# 6coils-1-discrete.net
KiCad netlist of a schematic drawn in EasyEDA
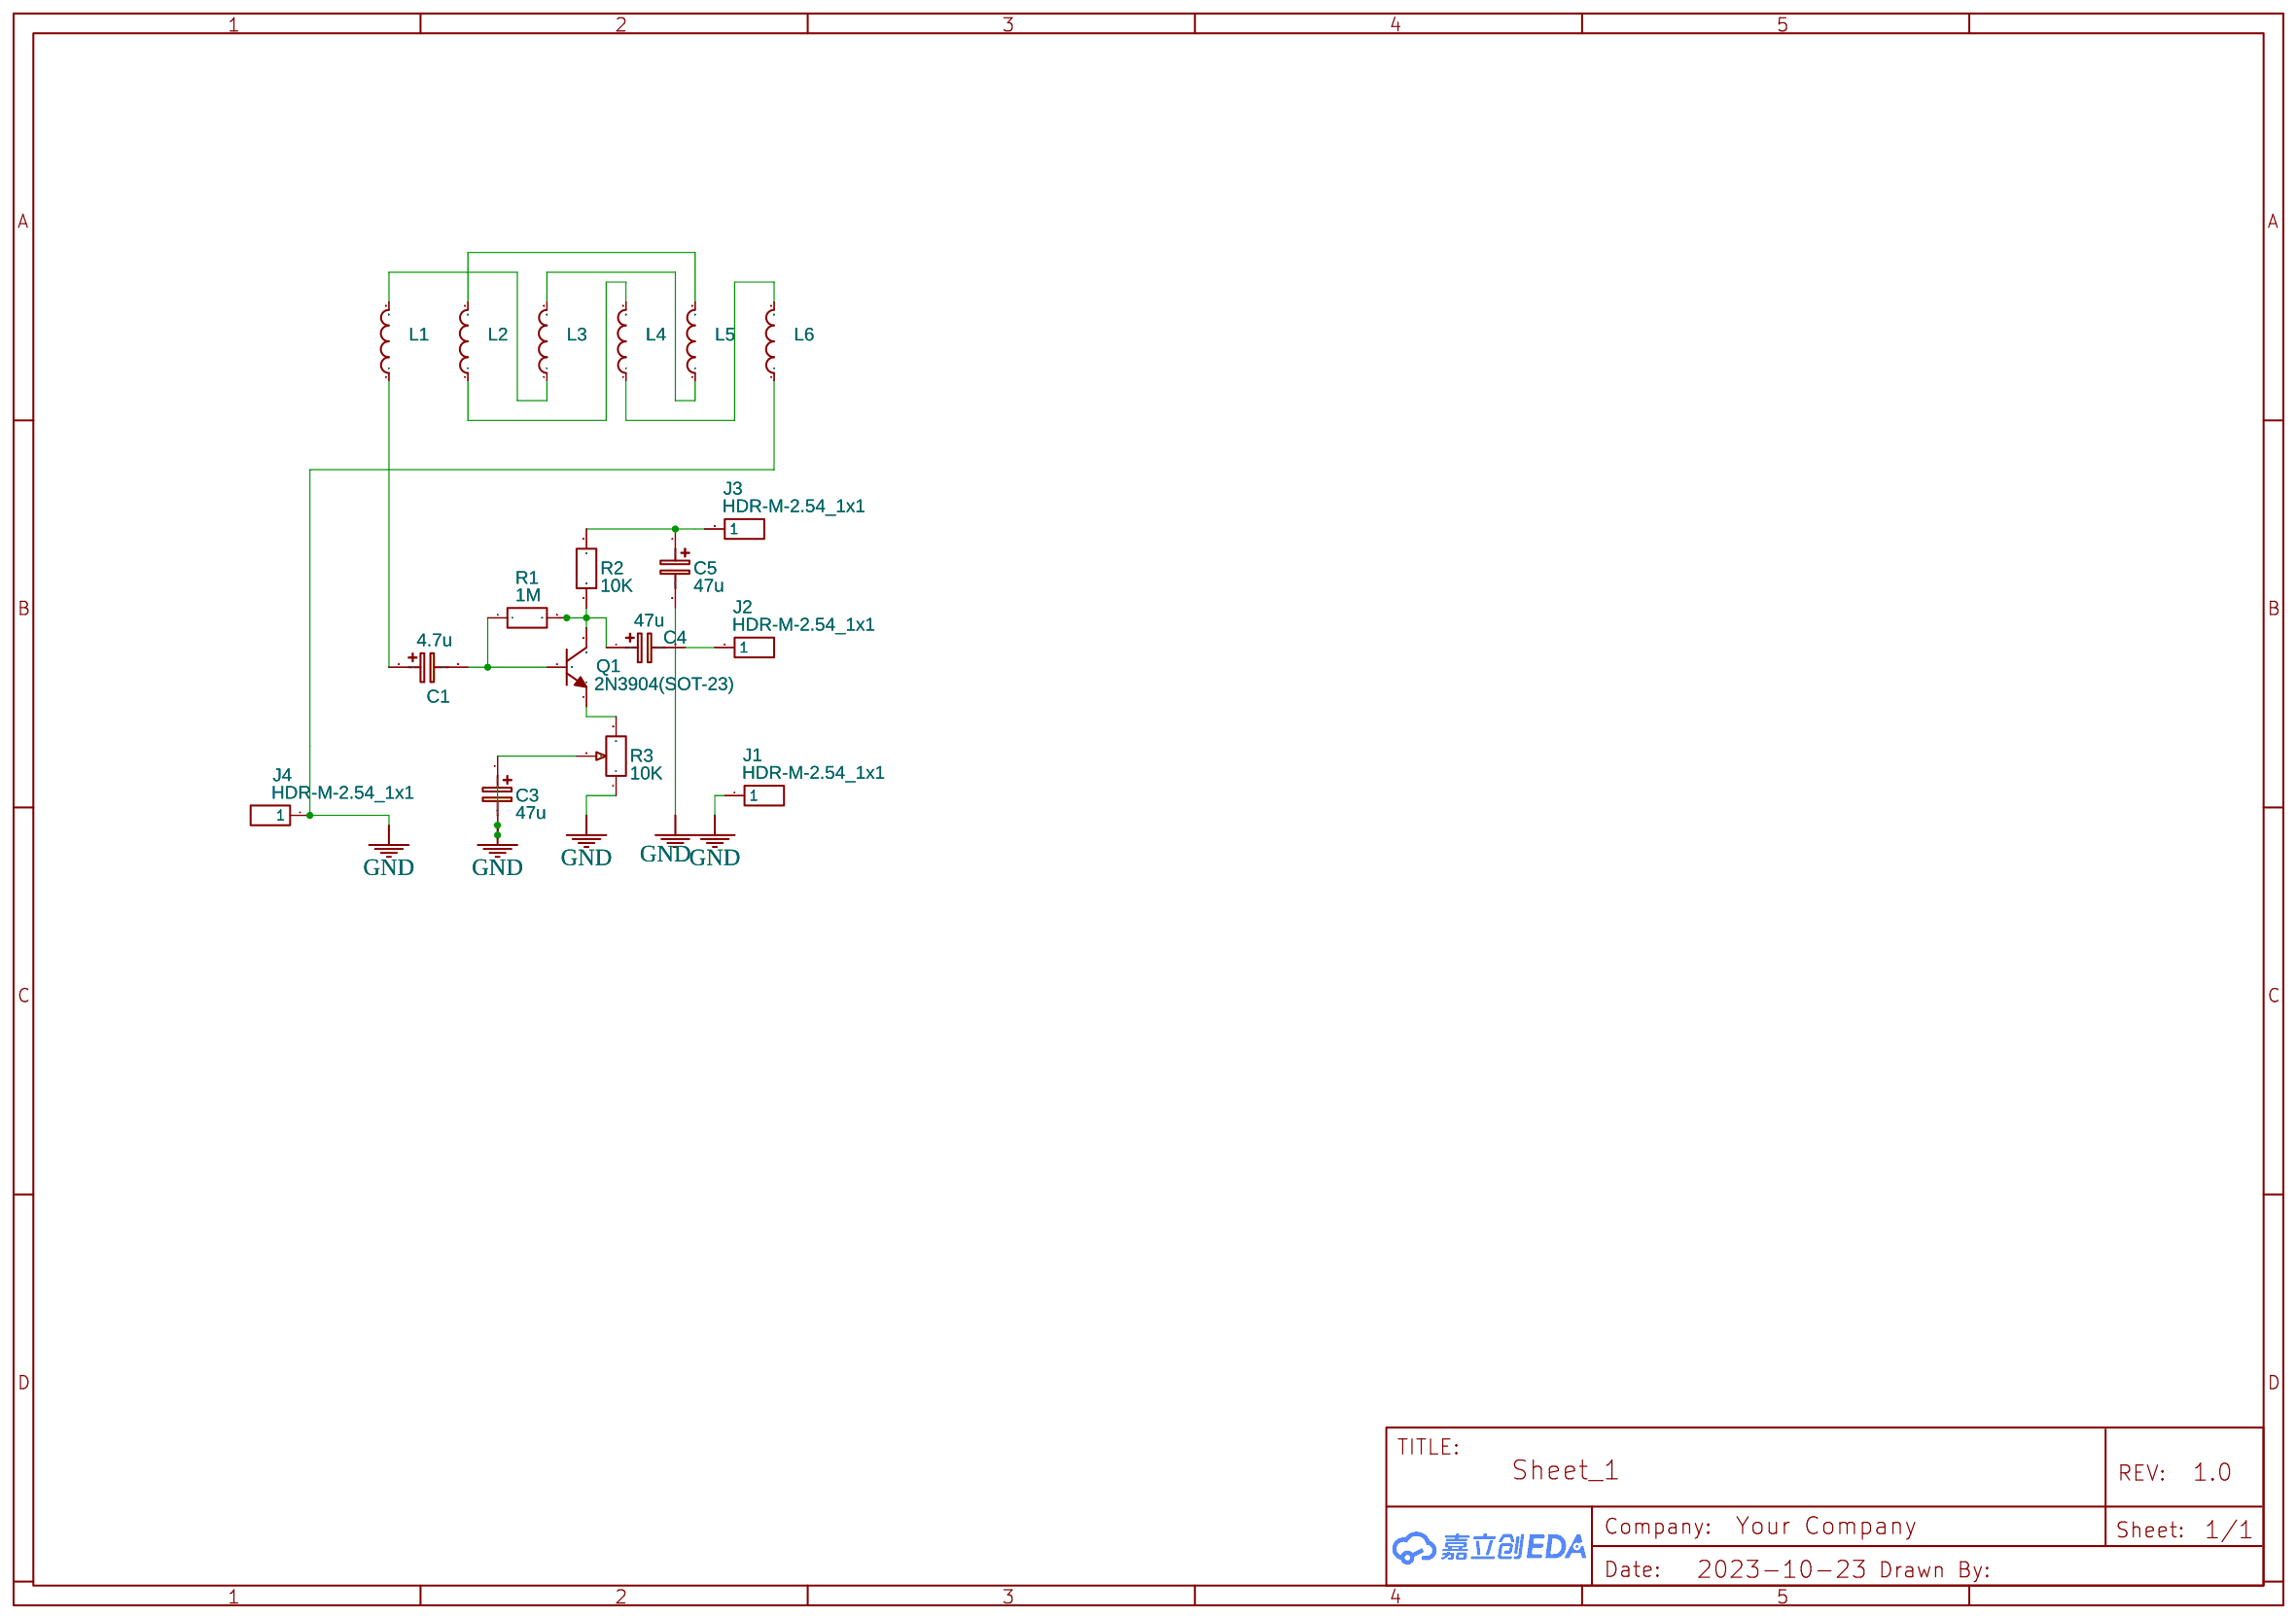
[diagram p0: schematic sheet]

(export (version "E")
  (design (tool "Eeschema 10.0.6"))
  (components
    (comp (ref "C1") (value "4.7u") (libsource (lib "") (part "C_Tan_SMD_A_EU_1")))
    (comp (ref "C3") (value "47u") (libsource (lib "") (part "C_Tan_SMD_A_EU_2")))
    (comp (ref "C4") (value "47u") (libsource (lib "") (part "C_Tan_SMD_A_EU_3")))
    (comp (ref "C5") (value "47u") (libsource (lib "") (part "C_Tan_SMD_A_EU")))
    (comp (ref "J1")
      (value "HDR-M-2.54_1x1")
      (fields (field (name "BOM_Supplier Part") "C81276"))
      (libsource (lib "") (part "HDR-M-2.54_1x1"))
    )
    (comp (ref "J2")
      (value "HDR-M-2.54_1x1")
      (fields (field (name "BOM_Supplier Part") "C81276"))
      (libsource (lib "") (part "HDR-M-2.54_1x1"))
    )
    (comp (ref "J3")
      (value "HDR-M-2.54_1x1")
      (fields (field (name "BOM_Supplier Part") "C81276"))
      (libsource (lib "") (part "HDR-M-2.54_1x1"))
    )
    (comp (ref "J4")
      (value "HDR-M-2.54_1x1")
      (fields (field (name "BOM_Supplier Part") "C81276"))
      (libsource (lib "") (part "HDR-M-2.54_1x1_1"))
    )
    (comp (ref "L1")
      (value "INDUCTOR_SMD:L_COILCRAFT_XXL4040")
      (fields (field (name "Manufacturer Part") "Inductor_SMD:L_Coilcraft_XxL4040"))
      (libsource (lib "") (part "INDUCTOR_SMD{colon}L_COILCRAFT_XXL4040_1"))
    )
    (comp (ref "L2")
      (value "INDUCTOR_SMD:L_COILCRAFT_XXL4040")
      (fields (field (name "Manufacturer Part") "Inductor_SMD:L_Coilcraft_XxL4040"))
      (libsource (lib "") (part "INDUCTOR_SMD{colon}L_COILCRAFT_XXL4040_1"))
    )
    (comp (ref "L3")
      (value "INDUCTOR_SMD:L_COILCRAFT_XXL4040")
      (fields (field (name "Manufacturer Part") "Inductor_SMD:L_Coilcraft_XxL4040"))
      (libsource (lib "") (part "INDUCTOR_SMD{colon}L_COILCRAFT_XXL4040"))
    )
    (comp (ref "L4")
      (value "INDUCTOR_SMD:L_COILCRAFT_XXL4040")
      (fields (field (name "Manufacturer Part") "Inductor_SMD:L_Coilcraft_XxL4040"))
      (libsource (lib "") (part "INDUCTOR_SMD{colon}L_COILCRAFT_XXL4040"))
    )
    (comp (ref "L5")
      (value "INDUCTOR_SMD:L_COILCRAFT_XXL4040")
      (fields (field (name "Manufacturer Part") "Inductor_SMD:L_Coilcraft_XxL4040"))
      (libsource (lib "") (part "INDUCTOR_SMD{colon}L_COILCRAFT_XXL4040"))
    )
    (comp (ref "L6")
      (value "INDUCTOR_SMD:L_COILCRAFT_XXL4040")
      (fields (field (name "Manufacturer Part") "Inductor_SMD:L_Coilcraft_XxL4040"))
      (libsource (lib "") (part "INDUCTOR_SMD{colon}L_COILCRAFT_XXL4040"))
    )
    (comp (ref "Q1")
      (value "2N3904(SOT-23)")
      (fields
        (field (name "BOM_Manufacturer Part") "2n3904S-RTK/PS")
        (field (name "BOM_Supplier Part") "C18536")
      )
      (libsource (lib "") (part "2N3904(SOT-23)"))
    )
    (comp (ref "R1") (value "1M") (libsource (lib "") (part "R_0603_EU")))
    (comp (ref "R2") (value "10K") (libsource (lib "") (part "R_0603_EU_1")))
    (comp (ref "R3")
      (value "10K")
      (fields (field (name "Manufacturer Part") "RM063-103 10K") (field (name "Manufacturer") "JML"))
      (libsource (lib "") (part "RM063-103 10K"))
    )
  )
  (nets
    (net (code "1") (name "GND") (class "Default")
      (node (ref "C3") (pin "2") (pinfunction "2_2") (pintype "unspecified"))
      (node (ref "C5") (pin "2") (pinfunction "2_2") (pintype "unspecified"))
      (node (ref "J1") (pin "1") (pinfunction "1_1") (pintype "input"))
      (node (ref "J4") (pin "1") (pinfunction "1_1") (pintype "input"))
      (node (ref "L6") (pin "1") (pinfunction "1_1") (pintype "unspecified"))
      (node (ref "R3") (pin "1") (pinfunction "1_1") (pintype "input"))
    )
    (net (code "2") (name "Net-(C1-Pad1)") (class "Default")
      (node (ref "C1") (pin "1") (pinfunction "1_1") (pintype "unspecified"))
      (node (ref "L1") (pin "1") (pinfunction "1_1") (pintype "unspecified"))
    )
    (net (code "3") (name "Net-(C3-Pad1)") (class "Default")
      (node (ref "C3") (pin "1") (pinfunction "1_1") (pintype "unspecified"))
      (node (ref "R3") (pin "2") (pinfunction "2_2") (pintype "input"))
    )
    (net (code "4") (name "Net-(C4-Pad2)") (class "Default")
      (node (ref "C4") (pin "2") (pinfunction "2_2") (pintype "unspecified"))
      (node (ref "J2") (pin "1") (pinfunction "1_1") (pintype "input"))
    )
    (net (code "5") (name "Net-(C5-Pad1)") (class "Default")
      (node (ref "C5") (pin "1") (pinfunction "1_1") (pintype "unspecified"))
      (node (ref "J3") (pin "1") (pinfunction "1_1") (pintype "input"))
      (node (ref "R2") (pin "2") (pinfunction "2_2") (pintype "unspecified"))
    )
    (net (code "6") (name "Net-(L1-Pad2)") (class "Default")
      (node (ref "L1") (pin "2") (pinfunction "2_2") (pintype "unspecified"))
      (node (ref "L3") (pin "1") (pinfunction "1_1") (pintype "unspecified"))
    )
    (net (code "7") (name "Net-(L2-Pad1)") (class "Default")
      (node (ref "L2") (pin "1") (pinfunction "1_1") (pintype "unspecified"))
      (node (ref "L4") (pin "2") (pinfunction "2_2") (pintype "unspecified"))
    )
    (net (code "8") (name "Net-(L2-Pad2)") (class "Default")
      (node (ref "L2") (pin "2") (pinfunction "2_2") (pintype "unspecified"))
      (node (ref "L5") (pin "2") (pinfunction "2_2") (pintype "unspecified"))
    )
    (net (code "9") (name "Net-(L3-Pad2)") (class "Default")
      (node (ref "L3") (pin "2") (pinfunction "2_2") (pintype "unspecified"))
      (node (ref "L5") (pin "1") (pinfunction "1_1") (pintype "unspecified"))
    )
    (net (code "10") (name "Net-(L4-Pad1)") (class "Default")
      (node (ref "L4") (pin "1") (pinfunction "1_1") (pintype "unspecified"))
      (node (ref "L6") (pin "2") (pinfunction "2_2") (pintype "unspecified"))
    )
    (net (code "11") (name "Net-(Q1-B)") (class "Default")
      (node (ref "C1") (pin "2") (pinfunction "2_2") (pintype "unspecified"))
      (node (ref "Q1") (pin "2") (pinfunction "B_2") (pintype "input"))
      (node (ref "R1") (pin "1") (pinfunction "1_1") (pintype "unspecified"))
    )
    (net (code "12") (name "Net-(Q1-C)") (class "Default")
      (node (ref "C4") (pin "1") (pinfunction "1_1") (pintype "unspecified"))
      (node (ref "Q1") (pin "3") (pinfunction "C_3") (pintype "input"))
      (node (ref "R1") (pin "2") (pinfunction "2_2") (pintype "unspecified"))
      (node (ref "R2") (pin "1") (pinfunction "1_1") (pintype "unspecified"))
    )
    (net (code "13") (name "Net-(Q1-E)") (class "Default")
      (node (ref "Q1") (pin "1") (pinfunction "E_1") (pintype "input"))
      (node (ref "R3") (pin "3") (pinfunction "3_3") (pintype "input"))
    )
  )
)
